# alarm.net
KiCad netlist of a schematic drawn in EAGLE
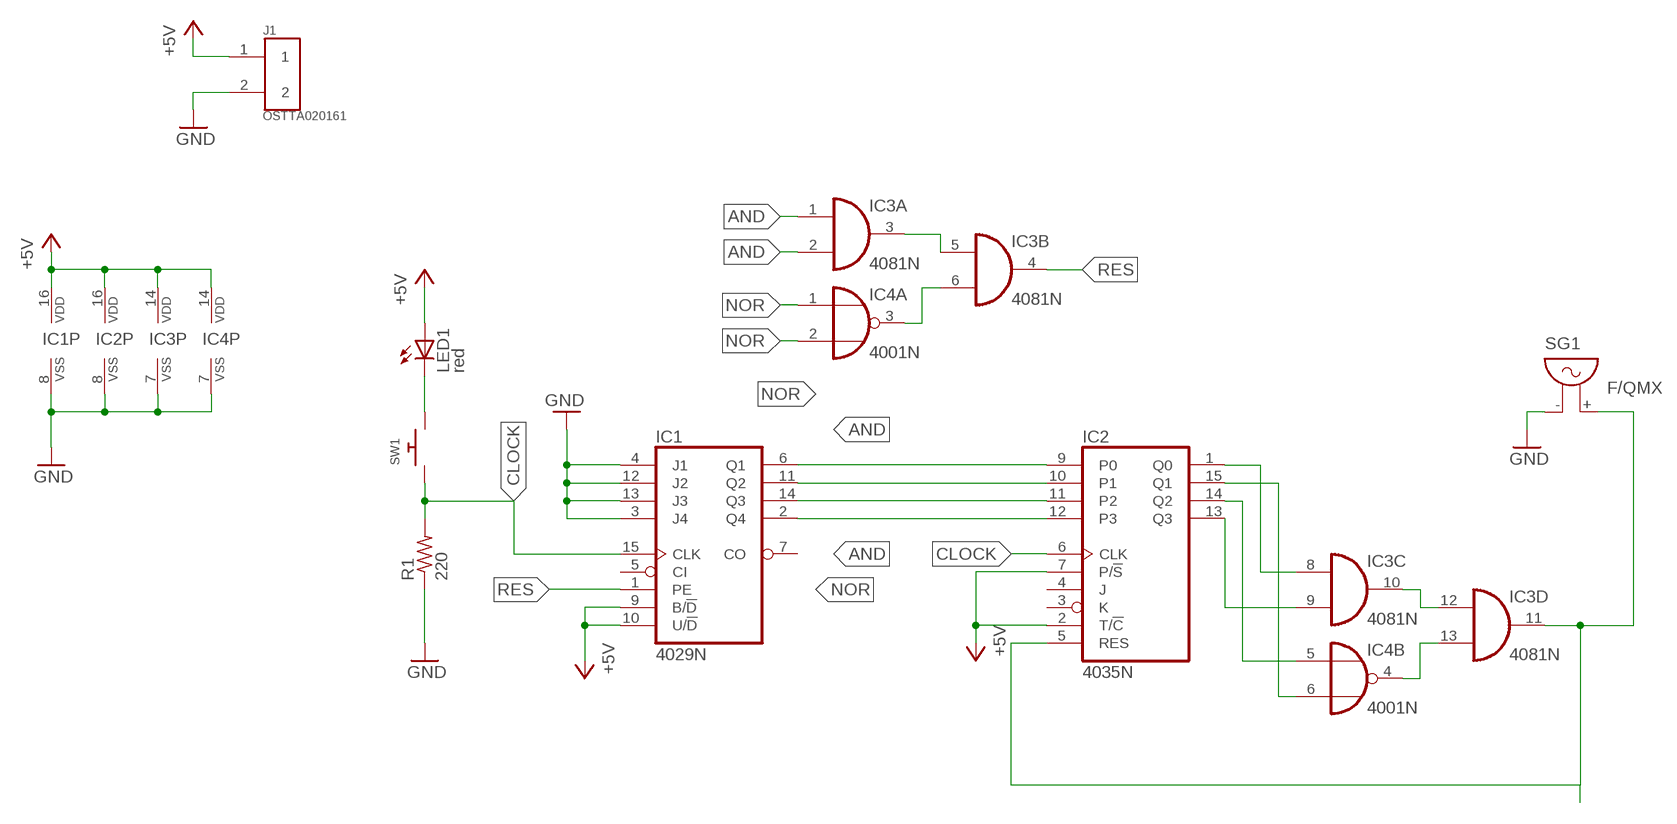
[diagram p0: schematic, sheet 1]

(export (version "E")
  (design (tool "Eeschema 10.0.6"))
  (components
    (comp (ref "IC1")
      (value "4029N")
      (footprint "eagle-import:DIL16")
      (libsource (lib "eagle-import") (part "4029N"))
    )
    (comp (ref "IC2")
      (value "4035N")
      (footprint "eagle-import:DIL16")
      (libsource (lib "eagle-import") (part "4035N"))
    )
    (comp (ref "IC3")
      (value "4081N")
      (footprint "eagle-import:DIL14")
      (libsource (lib "eagle-import") (part "4081N"))
    )
    (comp (ref "IC4")
      (value "4001N")
      (footprint "eagle-import:DIL14")
      (libsource (lib "eagle-import") (part "4001N"))
    )
    (comp (ref "J1")
      (value "OSTTA020161")
      (footprint "eagle-import:OST_OSTTA020161")
      (fields (field (name "MF") "On Shore Technology Inc."))
      (libsource (lib "eagle-import") (part "OSTTA020161"))
    )
    (comp (ref "LED1")
      (value "red")
      (footprint "eagle-import:LED3MM")
      (libsource (lib "eagle-import") (part "LED3MM"))
    )
    (comp (ref "R1")
      (value "220")
      (footprint "eagle-import:0204V")
      (libsource (lib "eagle-import") (part "R-US_0204/2V"))
    )
    (comp (ref "SG1")
      (value "F/QMX")
      (footprint "eagle-import:F_QMX")
      (libsource (lib "eagle-import") (part "F/QMX"))
    )
    (comp (ref "SW1")
      (value "SWITCH_PUSHBUTTONEVQ-PE")
      (footprint "eagle-import:TACT_PANA-EVQ")
      (libsource (lib "eagle-import") (part "SWITCH_PUSHBUTTONEVQ-PE"))
    )
  )
  (nets
    (net (code "1") (name "+5V") (class "Default")
      (node (ref "IC1") (pin "10") (pinfunction "U/~{D}_10") (pintype "input"))
      (node (ref "IC1") (pin "16") (pinfunction "VDD_16") (pintype "power_in"))
      (node (ref "IC1") (pin "9") (pinfunction "B/~{D}_9") (pintype "input"))
      (node (ref "IC2") (pin "16") (pinfunction "VDD_16") (pintype "power_in"))
      (node (ref "IC2") (pin "2") (pinfunction "T/~{C}_2") (pintype "input"))
      (node (ref "IC2") (pin "7") (pinfunction "P/~{S}_7") (pintype "input"))
      (node (ref "IC3") (pin "14") (pinfunction "VDD_14") (pintype "power_in"))
      (node (ref "IC4") (pin "14") (pinfunction "VDD_14") (pintype "power_in"))
      (node (ref "J1") (pin "1") (pinfunction "1_1") (pintype "passive"))
      (node (ref "LED1") (pin "A") (pinfunction "A_A") (pintype "passive"))
    )
    (net (code "2") (name "AND") (class "Default")
      (node (ref "IC1") (pin "11") (pinfunction "Q2_11") (pintype "output"))
      (node (ref "IC1") (pin "2") (pinfunction "Q4_2") (pintype "output"))
      (node (ref "IC2") (pin "10") (pinfunction "P1_10") (pintype "input"))
      (node (ref "IC2") (pin "12") (pinfunction "P3_12") (pintype "input"))
      (node (ref "IC3") (pin "1") (pinfunction "I0_1") (pintype "input"))
      (node (ref "IC3") (pin "2") (pinfunction "I1_2") (pintype "input"))
    )
    (net (code "3") (name "CLOCK") (class "Default")
      (node (ref "IC1") (pin "15") (pinfunction "CLK_15") (pintype "input"))
      (node (ref "IC2") (pin "6") (pinfunction "CLK_6") (pintype "input"))
      (node (ref "R1") (pin "2") (pinfunction "2_2") (pintype "passive"))
      (node (ref "SW1") (pin "P$1") (pinfunction "P$1_P$1") (pintype "passive"))
    )
    (net (code "4") (name "GND") (class "Default")
      (node (ref "IC1") (pin "12") (pinfunction "J2_12") (pintype "input"))
      (node (ref "IC1") (pin "13") (pinfunction "J3_13") (pintype "input"))
      (node (ref "IC1") (pin "3") (pinfunction "J4_3") (pintype "input"))
      (node (ref "IC1") (pin "4") (pinfunction "J1_4") (pintype "input"))
      (node (ref "IC1") (pin "8") (pinfunction "VSS_8") (pintype "power_in"))
      (node (ref "IC2") (pin "8") (pinfunction "VSS_8") (pintype "power_in"))
      (node (ref "IC3") (pin "7") (pinfunction "VSS_7") (pintype "power_in"))
      (node (ref "IC4") (pin "7") (pinfunction "VSS_7") (pintype "power_in"))
      (node (ref "J1") (pin "2") (pinfunction "2_2") (pintype "passive"))
      (node (ref "R1") (pin "1") (pinfunction "1_1") (pintype "passive"))
      (node (ref "SG1") (pin "-") (pinfunction "1_-") (pintype "passive"))
    )
    (net (code "5") (name "NOR") (class "Default")
      (node (ref "IC1") (pin "14") (pinfunction "Q3_14") (pintype "output"))
      (node (ref "IC1") (pin "6") (pinfunction "Q1_6") (pintype "output"))
      (node (ref "IC2") (pin "11") (pinfunction "P2_11") (pintype "input"))
      (node (ref "IC2") (pin "9") (pinfunction "P0_9") (pintype "input"))
      (node (ref "IC4") (pin "1") (pinfunction "I0_1") (pintype "input"))
      (node (ref "IC4") (pin "2") (pinfunction "I1_2") (pintype "input"))
    )
    (net (code "6") (name "Net-(IC2A-Q0)") (class "Default")
      (node (ref "IC2") (pin "1") (pinfunction "Q0_1") (pintype "output"))
      (node (ref "IC3") (pin "8") (pinfunction "I0_8") (pintype "input"))
    )
    (net (code "7") (name "Net-(IC2A-Q1)") (class "Default")
      (node (ref "IC2") (pin "15") (pinfunction "Q1_15") (pintype "output"))
      (node (ref "IC4") (pin "6") (pinfunction "I1_6") (pintype "input"))
    )
    (net (code "8") (name "Net-(IC2A-Q2)") (class "Default")
      (node (ref "IC2") (pin "14") (pinfunction "Q2_14") (pintype "output"))
      (node (ref "IC4") (pin "5") (pinfunction "I0_5") (pintype "input"))
    )
    (net (code "9") (name "Net-(IC2A-Q3)") (class "Default")
      (node (ref "IC2") (pin "13") (pinfunction "Q3_13") (pintype "output"))
      (node (ref "IC3") (pin "9") (pinfunction "I1_9") (pintype "input"))
    )
    (net (code "10") (name "Net-(IC2A-RES)") (class "Default")
      (node (ref "IC2") (pin "5") (pinfunction "RES_5") (pintype "input"))
      (node (ref "IC3") (pin "11") (pinfunction "O_11") (pintype "output"))
      (node (ref "SG1") (pin "+") (pinfunction "2_+") (pintype "passive"))
    )
    (net (code "11") (name "Net-(IC3A-O)") (class "Default")
      (node (ref "IC3") (pin "3") (pinfunction "O_3") (pintype "output"))
      (node (ref "IC3") (pin "5") (pinfunction "I0_5") (pintype "input"))
    )
    (net (code "12") (name "Net-(IC3B-I1)") (class "Default")
      (node (ref "IC3") (pin "6") (pinfunction "I1_6") (pintype "input"))
      (node (ref "IC4") (pin "3") (pinfunction "O_3") (pintype "output"))
    )
    (net (code "13") (name "Net-(IC3C-O)") (class "Default")
      (node (ref "IC3") (pin "10") (pinfunction "O_10") (pintype "output"))
      (node (ref "IC3") (pin "12") (pinfunction "I0_12") (pintype "input"))
    )
    (net (code "14") (name "Net-(IC3D-I1)") (class "Default")
      (node (ref "IC3") (pin "13") (pinfunction "I1_13") (pintype "input"))
      (node (ref "IC4") (pin "4") (pinfunction "O_4") (pintype "output"))
    )
    (net (code "15") (name "Net-(LED1-C)") (class "Default")
      (node (ref "LED1") (pin "K") (pinfunction "C_K") (pintype "passive"))
      (node (ref "SW1") (pin "P$2") (pinfunction "P$2_P$2") (pintype "passive"))
    )
    (net (code "16") (name "RES") (class "Default")
      (node (ref "IC1") (pin "1") (pinfunction "PE_1") (pintype "input"))
      (node (ref "IC3") (pin "4") (pinfunction "O_4") (pintype "output"))
    )
    (net (code "17") (name "unconnected-(IC1A-CI-Pad5)") (class "Default")
      (node (ref "IC1") (pin "5") (pinfunction "CI_5") (pintype "input"))
    )
    (net (code "18") (name "unconnected-(IC1A-CO-Pad7)") (class "Default")
      (node (ref "IC1") (pin "7") (pinfunction "CO_7") (pintype "output"))
    )
    (net (code "19") (name "unconnected-(IC2A-J-Pad4)") (class "Default")
      (node (ref "IC2") (pin "4") (pinfunction "J_4") (pintype "input"))
    )
    (net (code "20") (name "unconnected-(IC2A-K-Pad3)") (class "Default")
      (node (ref "IC2") (pin "3") (pinfunction "K_3") (pintype "input"))
    )
  )
)
